# SW6124_A_C_LED.net
KiCad netlist of a schematic drawn in Altium Designer
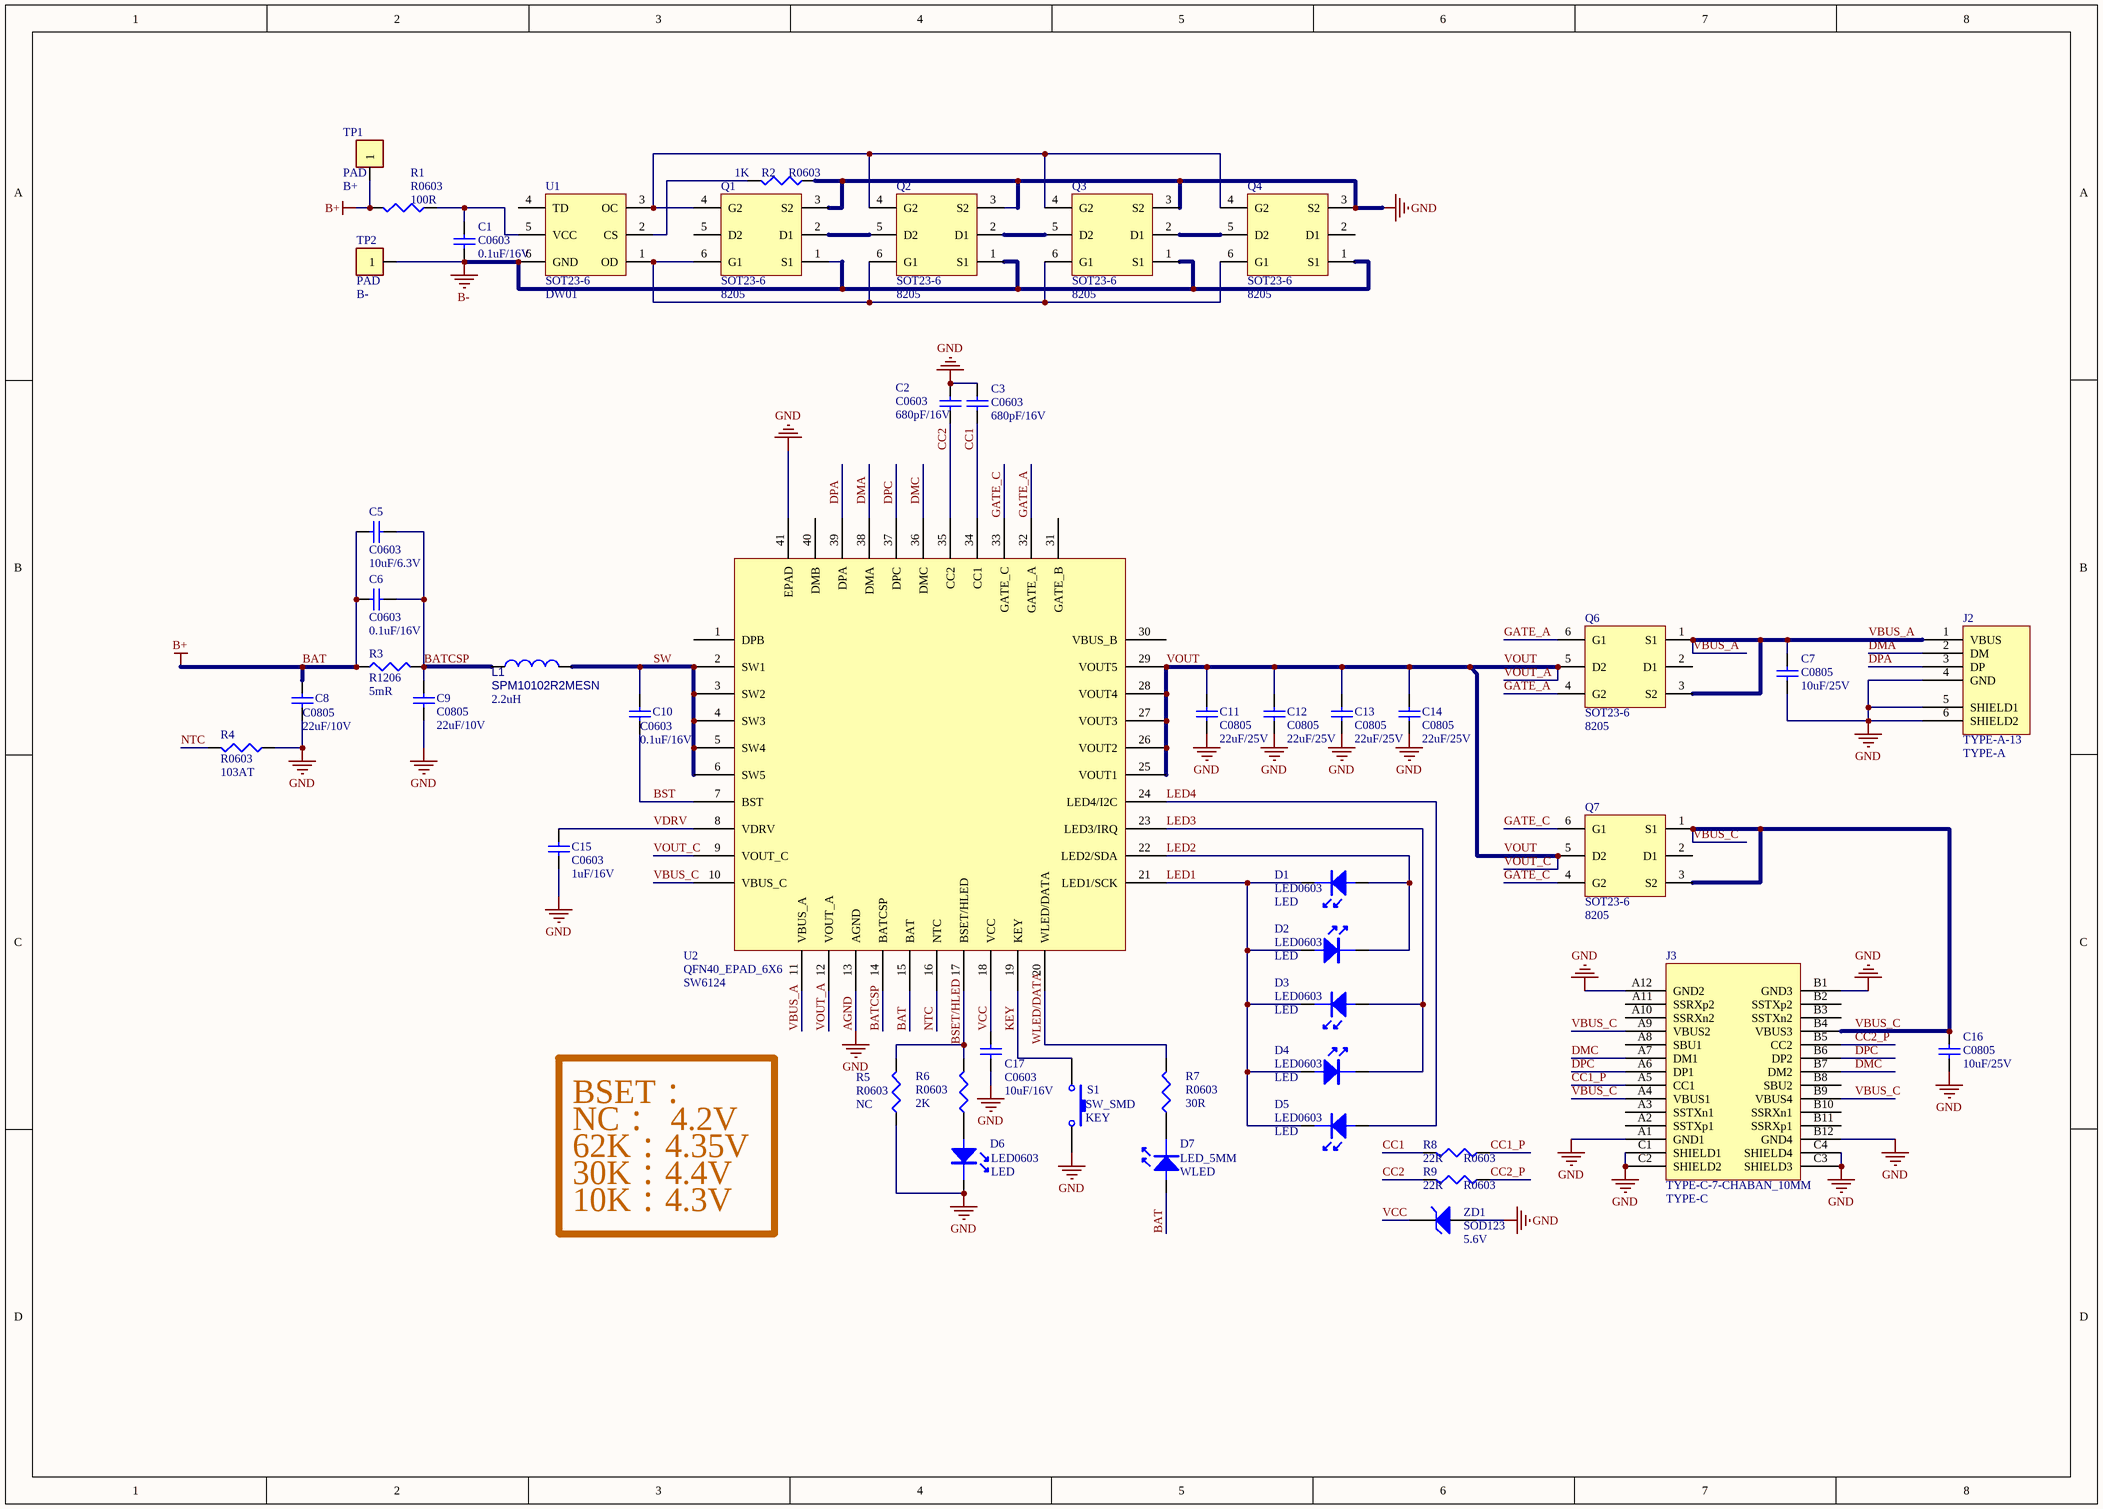
[diagram p0: SW6124+A+C+LED.SchDoc]

(export (version "E")
  (design (tool "Eeschema 10.0.6"))
  (components
    (comp (ref "C1")
      (value "C0603")
      (footprint "C0603")
      (description "Capacitor")
      (fields (field (name "ALTIUM_VALUE") "0.1uF/16V") (field (name "PUBLISHER") "Altium Limited"))
      (libsource (lib "*") (part "Cap"))
    )
    (comp (ref "C2")
      (value "C0603")
      (footprint "C0603")
      (description "Capacitor")
      (fields (field (name "ALTIUM_VALUE") "680pF/16V") (field (name "PUBLISHER") "Altium Limited"))
      (libsource (lib "*") (part "CAP0603"))
    )
    (comp (ref "C3")
      (value "C0603")
      (footprint "C0603")
      (description "Capacitor")
      (fields (field (name "ALTIUM_VALUE") "680pF/16V") (field (name "PUBLISHER") "Altium Limited"))
      (libsource (lib "*") (part "CAP0603"))
    )
    (comp (ref "C5")
      (value "C0603")
      (footprint "C0603")
      (description "Capacitor")
      (fields (field (name "ALTIUM_VALUE") "10uF/6.3V") (field (name "PUBLISHER") "Altium Limited"))
      (libsource (lib "*") (part "CAP0603"))
    )
    (comp (ref "C6")
      (value "C0603")
      (footprint "C0603")
      (description "Capacitor")
      (fields (field (name "ALTIUM_VALUE") "0.1uF/16V") (field (name "PUBLISHER") "Altium Limited"))
      (libsource (lib "*") (part "CAP0603"))
    )
    (comp (ref "C7")
      (value "C0805")
      (footprint "C0805")
      (description "Capacitor")
      (fields (field (name "ALTIUM_VALUE") "10uF/25V") (field (name "PUBLISHER") "Altium Limited"))
      (libsource (lib "*") (part "CAP0603"))
    )
    (comp (ref "C8")
      (value "C0805")
      (footprint "C0805")
      (description "Capacitor")
      (fields (field (name "ALTIUM_VALUE") "22uF/10V") (field (name "PUBLISHER") "Altium Limited"))
      (libsource (lib "*") (part "CAP0805"))
    )
    (comp (ref "C9")
      (value "C0805")
      (footprint "C0805")
      (description "Capacitor")
      (fields (field (name "ALTIUM_VALUE") "22uF/10V") (field (name "PUBLISHER") "Altium Limited"))
      (libsource (lib "*") (part "CAP0805"))
    )
    (comp (ref "C10")
      (value "C0603")
      (footprint "C0603")
      (description "Capacitor")
      (fields (field (name "ALTIUM_VALUE") "0.1uF/16V") (field (name "PUBLISHER") "Altium Limited"))
      (libsource (lib "*") (part "CAP0603"))
    )
    (comp (ref "C11")
      (value "C0805")
      (footprint "C0805")
      (description "Capacitor")
      (fields (field (name "ALTIUM_VALUE") "22uF/25V") (field (name "PUBLISHER") "Altium Limited"))
      (libsource (lib "*") (part "CAP0805"))
    )
    (comp (ref "C12")
      (value "C0805")
      (footprint "C0805")
      (description "Capacitor")
      (fields (field (name "ALTIUM_VALUE") "22uF/25V") (field (name "PUBLISHER") "Altium Limited"))
      (libsource (lib "*") (part "CAP0805"))
    )
    (comp (ref "C13")
      (value "C0805")
      (footprint "C0805")
      (description "Capacitor")
      (fields (field (name "ALTIUM_VALUE") "22uF/25V") (field (name "PUBLISHER") "Altium Limited"))
      (libsource (lib "*") (part "CAP0805"))
    )
    (comp (ref "C14")
      (value "C0805")
      (footprint "C0805")
      (description "Capacitor")
      (fields (field (name "ALTIUM_VALUE") "22uF/25V") (field (name "PUBLISHER") "Altium Limited"))
      (libsource (lib "*") (part "CAP0805"))
    )
    (comp (ref "C15")
      (value "C0603")
      (footprint "C0603")
      (description "Capacitor")
      (fields (field (name "ALTIUM_VALUE") "1uF/16V") (field (name "PUBLISHER") "Altium Limited"))
      (libsource (lib "*") (part "CAP0603"))
    )
    (comp (ref "C16")
      (value "C0805")
      (footprint "C0805")
      (description "Capacitor")
      (fields (field (name "ALTIUM_VALUE") "10uF/25V") (field (name "PUBLISHER") "Altium Limited"))
      (libsource (lib "*") (part "CAP0603"))
    )
    (comp (ref "C17")
      (value "C0603")
      (footprint "C0603")
      (description "Capacitor")
      (fields (field (name "ALTIUM_VALUE") "10uF/16V") (field (name "PUBLISHER") "Altium Limited"))
      (libsource (lib "*") (part "CAP0603"))
    )
    (comp (ref "D1") (value "LED") (footprint "LED0603") (libsource (lib "*") (part "LED")))
    (comp (ref "D2") (value "LED") (footprint "LED0603") (libsource (lib "*") (part "LED")))
    (comp (ref "D3") (value "LED") (footprint "LED0603") (libsource (lib "*") (part "LED")))
    (comp (ref "D4") (value "LED") (footprint "LED0603") (libsource (lib "*") (part "LED")))
    (comp (ref "D5") (value "LED") (footprint "LED0603") (libsource (lib "*") (part "LED")))
    (comp (ref "D6") (value "LED") (footprint "LED0603") (libsource (lib "*") (part "LED")))
    (comp (ref "D7")
      (value "WLED")
      (footprint "LED_5MM")
      (fields (field (name "FOOTPRINF") "LED_5MM") (field (name "Comment") "LED_5MM"))
      (libsource (lib "*") (part "LED"))
    )
    (comp (ref "J2")
      (value "TYPE-A")
      (footprint "TYPE-A-13")
      (fields (field (name "FOOTPRINF") "TYPE-A-13") (field (name "Comment") "TYPE-A-1"))
      (libsource (lib "*") (part "TYPE-A-1"))
    )
    (comp (ref "J3")
      (value "TYPE-C")
      (footprint "TYPE-C-7-CHABAN_10MM")
      (libsource (lib "*") (part "TYPE-C"))
    )
    (comp (ref "L1")
      (value "SPM10102R2MESN")
      (footprint "INDUCTOR_SPM1010")
      (fields (field (name "ALTIUM_VALUE") "2.2uH"))
      (libsource (lib "*") (part "INDUCTOR"))
    )
    (comp (ref "Q1")
      (value "8205")
      (footprint "SOT23-6")
      (fields (field (name "FOOTPRINF") "SOT23-6"))
      (libsource (lib "*") (part "8205B"))
    )
    (comp (ref "Q2")
      (value "8205")
      (footprint "SOT23-6")
      (fields (field (name "FOOTPRINF") "SOT23-6"))
      (libsource (lib "*") (part "8205B"))
    )
    (comp (ref "Q3")
      (value "8205")
      (footprint "SOT23-6")
      (fields (field (name "FOOTPRINF") "SOT23-6"))
      (libsource (lib "*") (part "8205B"))
    )
    (comp (ref "Q4")
      (value "8205")
      (footprint "SOT23-6")
      (fields (field (name "FOOTPRINF") "SOT23-6"))
      (libsource (lib "*") (part "8205B"))
    )
    (comp (ref "Q6")
      (value "8205")
      (footprint "SOT23-6")
      (fields (field (name "FOOTPRINF") "SOT23-6"))
      (libsource (lib "") (part "8205B_1"))
    )
    (comp (ref "Q7")
      (value "8205")
      (footprint "SOT23-6")
      (fields (field (name "FOOTPRINF") "SOT23-6"))
      (libsource (lib "") (part "8205B_1"))
    )
    (comp (ref "R1")
      (value "R0603")
      (footprint "R0603")
      (description "Resistor")
      (fields (field (name "ALTIUM_VALUE") "100R") (field (name "PUBLISHER") "Altium Limited"))
      (libsource (lib "*") (part "Res3"))
    )
    (comp (ref "R2")
      (value "R0603")
      (footprint "R0603")
      (description "Resistor")
      (fields (field (name "ALTIUM_VALUE") "1K") (field (name "PUBLISHER") "Altium Limited"))
      (libsource (lib "*") (part "Res3"))
    )
    (comp (ref "R3")
      (value "R1206")
      (footprint "R1206")
      (description "Resistor")
      (fields (field (name "ALTIUM_VALUE") "5mR") (field (name "PUBLISHER") "Altium Limited"))
      (libsource (lib "*") (part "RES"))
    )
    (comp (ref "R4")
      (value "R0603")
      (footprint "R0603")
      (description "Resistor")
      (fields (field (name "ALTIUM_VALUE") "103AT") (field (name "PUBLISHER") "Altium Limited"))
      (libsource (lib "*") (part "RES"))
    )
    (comp (ref "R5")
      (value "R0603")
      (footprint "R0603")
      (description "Resistor")
      (fields (field (name "ALTIUM_VALUE") "NC") (field (name "PUBLISHER") "Altium Limited"))
      (libsource (lib "*") (part "RES"))
    )
    (comp (ref "R6")
      (value "R0603")
      (footprint "R0603")
      (description "Resistor")
      (fields (field (name "ALTIUM_VALUE") "2K") (field (name "PUBLISHER") "Altium Limited"))
      (libsource (lib "*") (part "RES"))
    )
    (comp (ref "R7")
      (value "R0603")
      (footprint "R0603")
      (description "Resistor")
      (fields (field (name "ALTIUM_VALUE") "30R") (field (name "PUBLISHER") "Altium Limited"))
      (libsource (lib "*") (part "RES"))
    )
    (comp (ref "R8")
      (value "R0603")
      (footprint "R0603")
      (description "Resistor")
      (fields (field (name "ALTIUM_VALUE") "22R") (field (name "PUBLISHER") "Altium Limited"))
      (libsource (lib "*") (part "RES"))
    )
    (comp (ref "R9")
      (value "R0603")
      (footprint "R0603")
      (description "Resistor")
      (fields (field (name "ALTIUM_VALUE") "22R") (field (name "PUBLISHER") "Altium Limited"))
      (libsource (lib "*") (part "RES"))
    )
    (comp (ref "S1")
      (value "KEY")
      (footprint "SW_SMD")
      (fields (field (name "FOOTPRINF") "SW_SMD"))
      (libsource (lib "*") (part "SW K"))
    )
    (comp (ref "TP1") (value "B+") (footprint "PAD") (libsource (lib "") (part "Test Point_1")))
    (comp (ref "TP2") (value "B-") (footprint "PAD") (libsource (lib "*") (part "Test Point")))
    (comp (ref "U1")
      (value "DW01")
      (footprint "SOT23-6")
      (fields (field (name "FOOTPRINF") "SOT23-6"))
      (libsource (lib "*") (part "DW01"))
    )
    (comp (ref "U2")
      (value "SW6124")
      (footprint "QFN40_EPAD_6X6")
      (libsource (lib "TEST") (part "SW6106_AFC"))
    )
    (comp (ref "ZD1")
      (value "SOD123")
      (footprint "SOD-123")
      (description "Zener Diode")
      (fields (field (name "ALTIUM_UNNAMED_1") "5.6V"))
      (libsource (lib "Miscellaneous Devices") (part "D Zener"))
    )
  )
  (nets
    (net (code "1") (name "/BATCSP") (class "Default")
      (node (ref "C5") (pin "2") (pinfunction "2_2") (pintype "passive"))
      (node (ref "C6") (pin "2") (pinfunction "2_2") (pintype "passive"))
      (node (ref "C9") (pin "2") (pinfunction "2_2") (pintype "passive"))
      (node (ref "L1") (pin "1") (pinfunction "1_1") (pintype "passive"))
      (node (ref "R3") (pin "2") (pinfunction "2_2") (pintype "passive"))
      (node (ref "U2") (pin "14") (pinfunction "BATCSP_14") (pintype "passive"))
    )
    (net (code "2") (name "/BSET{slash}HLED") (class "Default")
      (node (ref "R5") (pin "2") (pinfunction "2_2") (pintype "passive"))
      (node (ref "R6") (pin "2") (pinfunction "2_2") (pintype "passive"))
      (node (ref "U2") (pin "17") (pinfunction "BSET/HLED_17") (pintype "passive"))
    )
    (net (code "3") (name "/BST") (class "Default")
      (node (ref "C10") (pin "1") (pinfunction "1_1") (pintype "passive"))
      (node (ref "U2") (pin "7") (pinfunction "BST_7") (pintype "passive"))
    )
    (net (code "4") (name "/CC1") (class "Default")
      (node (ref "C3") (pin "1") (pinfunction "1_1") (pintype "passive"))
      (node (ref "R8") (pin "2") (pinfunction "2_2") (pintype "passive"))
      (node (ref "U2") (pin "34") (pinfunction "CC1_34") (pintype "passive"))
    )
    (net (code "5") (name "/CC1_P") (class "Default")
      (node (ref "J3") (pin "A5") (pinfunction "CC1_A5") (pintype "passive"))
      (node (ref "R8") (pin "1") (pinfunction "1_1") (pintype "passive"))
    )
    (net (code "6") (name "/CC2") (class "Default")
      (node (ref "C2") (pin "1") (pinfunction "1_1") (pintype "passive"))
      (node (ref "R9") (pin "2") (pinfunction "2_2") (pintype "passive"))
      (node (ref "U2") (pin "35") (pinfunction "CC2_35") (pintype "passive"))
    )
    (net (code "7") (name "/CC2_P") (class "Default")
      (node (ref "J3") (pin "B5") (pinfunction "CC2_B5") (pintype "passive"))
      (node (ref "R9") (pin "1") (pinfunction "1_1") (pintype "passive"))
    )
    (net (code "8") (name "/DMA") (class "Default")
      (node (ref "J2") (pin "2") (pinfunction "DM_2") (pintype "passive"))
      (node (ref "U2") (pin "38") (pinfunction "DMA_38") (pintype "passive"))
    )
    (net (code "9") (name "/DMC") (class "Default")
      (node (ref "J3") (pin "A7") (pinfunction "DM1_A7") (pintype "passive"))
      (node (ref "J3") (pin "B7") (pinfunction "DM2_B7") (pintype "passive"))
      (node (ref "U2") (pin "36") (pinfunction "DMC_36") (pintype "passive"))
    )
    (net (code "10") (name "/DPA") (class "Default")
      (node (ref "J2") (pin "3") (pinfunction "DP_3") (pintype "passive"))
      (node (ref "U2") (pin "39") (pinfunction "DPA_39") (pintype "passive"))
    )
    (net (code "11") (name "/DPC") (class "Default")
      (node (ref "J3") (pin "A6") (pinfunction "DP1_A6") (pintype "passive"))
      (node (ref "J3") (pin "B6") (pinfunction "DP2_B6") (pintype "passive"))
      (node (ref "U2") (pin "37") (pinfunction "DPC_37") (pintype "passive"))
    )
    (net (code "12") (name "/GATE_A") (class "Default")
      (node (ref "Q6") (pin "4") (pinfunction "G2_4") (pintype "passive"))
      (node (ref "Q6") (pin "6") (pinfunction "G1_6") (pintype "passive"))
      (node (ref "U2") (pin "32") (pinfunction "GATE_A_32") (pintype "passive"))
    )
    (net (code "13") (name "/GATE_C") (class "Default")
      (node (ref "Q7") (pin "4") (pinfunction "G2_4") (pintype "passive"))
      (node (ref "Q7") (pin "6") (pinfunction "G1_6") (pintype "passive"))
      (node (ref "U2") (pin "33") (pinfunction "GATE_C_33") (pintype "passive"))
    )
    (net (code "14") (name "/KEY") (class "Default")
      (node (ref "S1") (pin "1") (pinfunction "1_1") (pintype "passive"))
      (node (ref "U2") (pin "19") (pinfunction "KEY_19") (pintype "passive"))
    )
    (net (code "15") (name "/LED1") (class "Default")
      (node (ref "D1") (pin "2") (pinfunction "K_2") (pintype "passive"))
      (node (ref "D2") (pin "1") (pinfunction "A_1") (pintype "passive"))
      (node (ref "D3") (pin "2") (pinfunction "K_2") (pintype "passive"))
      (node (ref "D4") (pin "1") (pinfunction "A_1") (pintype "passive"))
      (node (ref "D5") (pin "2") (pinfunction "K_2") (pintype "passive"))
      (node (ref "U2") (pin "21") (pinfunction "LED1/SCK_21") (pintype "passive"))
    )
    (net (code "16") (name "/LED2") (class "Default")
      (node (ref "D1") (pin "1") (pinfunction "A_1") (pintype "passive"))
      (node (ref "D2") (pin "2") (pinfunction "K_2") (pintype "passive"))
      (node (ref "U2") (pin "22") (pinfunction "LED2/SDA_22") (pintype "passive"))
    )
    (net (code "17") (name "/LED3") (class "Default")
      (node (ref "D3") (pin "1") (pinfunction "A_1") (pintype "passive"))
      (node (ref "D4") (pin "2") (pinfunction "K_2") (pintype "passive"))
      (node (ref "U2") (pin "23") (pinfunction "LED3/IRQ_23") (pintype "passive"))
    )
    (net (code "18") (name "/LED4") (class "Default")
      (node (ref "D5") (pin "1") (pinfunction "A_1") (pintype "passive"))
      (node (ref "U2") (pin "24") (pinfunction "LED4/I2C_24") (pintype "passive"))
    )
    (net (code "19") (name "/NTC") (class "Default")
      (node (ref "R4") (pin "2") (pinfunction "2_2") (pintype "passive"))
      (node (ref "U2") (pin "16") (pinfunction "NTC_16") (pintype "passive"))
    )
    (net (code "20") (name "/SW") (class "Default")
      (node (ref "C10") (pin "2") (pinfunction "2_2") (pintype "passive"))
      (node (ref "L1") (pin "2") (pinfunction "2_2") (pintype "passive"))
      (node (ref "U2") (pin "2") (pinfunction "SW1_2") (pintype "passive"))
      (node (ref "U2") (pin "3") (pinfunction "SW2_3") (pintype "passive"))
      (node (ref "U2") (pin "4") (pinfunction "SW3_4") (pintype "passive"))
      (node (ref "U2") (pin "5") (pinfunction "SW4_5") (pintype "passive"))
      (node (ref "U2") (pin "6") (pinfunction "SW5_6") (pintype "passive"))
    )
    (net (code "21") (name "/VBUS_A") (class "Default")
      (node (ref "C7") (pin "2") (pinfunction "2_2") (pintype "passive"))
      (node (ref "J2") (pin "1") (pinfunction "VBUS_1") (pintype "passive"))
      (node (ref "Q6") (pin "1") (pinfunction "S1_1") (pintype "passive"))
      (node (ref "Q6") (pin "3") (pinfunction "S2_3") (pintype "passive"))
      (node (ref "U2") (pin "11") (pinfunction "VBUS_A_11") (pintype "passive"))
    )
    (net (code "22") (name "/VBUS_C") (class "Default")
      (node (ref "C16") (pin "2") (pinfunction "2_2") (pintype "passive"))
      (node (ref "J3") (pin "A4") (pinfunction "VBUS1_A4") (pintype "passive"))
      (node (ref "J3") (pin "A9") (pinfunction "VBUS2_A9") (pintype "passive"))
      (node (ref "J3") (pin "B4") (pinfunction "VBUS3_B4") (pintype "passive"))
      (node (ref "J3") (pin "B9") (pinfunction "VBUS4_B9") (pintype "passive"))
      (node (ref "Q7") (pin "1") (pinfunction "S1_1") (pintype "passive"))
      (node (ref "Q7") (pin "3") (pinfunction "S2_3") (pintype "passive"))
      (node (ref "U2") (pin "10") (pinfunction "VBUS_C_10") (pintype "passive"))
    )
    (net (code "23") (name "/VCC") (class "Default")
      (node (ref "C17") (pin "2") (pinfunction "2_2") (pintype "passive"))
      (node (ref "U2") (pin "18") (pinfunction "VCC_18") (pintype "passive"))
      (node (ref "ZD1") (pin "2") (pinfunction "K_2") (pintype "passive"))
    )
    (net (code "24") (name "/VDRV") (class "Default")
      (node (ref "C15") (pin "2") (pinfunction "2_2") (pintype "passive"))
      (node (ref "U2") (pin "8") (pinfunction "VDRV_8") (pintype "passive"))
    )
    (net (code "25") (name "/VOUT") (class "Default")
      (node (ref "C11") (pin "2") (pinfunction "2_2") (pintype "passive"))
      (node (ref "C12") (pin "2") (pinfunction "2_2") (pintype "passive"))
      (node (ref "C13") (pin "2") (pinfunction "2_2") (pintype "passive"))
      (node (ref "C14") (pin "2") (pinfunction "2_2") (pintype "passive"))
      (node (ref "Q6") (pin "5") (pinfunction "D2_5") (pintype "passive"))
      (node (ref "Q7") (pin "5") (pinfunction "D2_5") (pintype "passive"))
      (node (ref "U2") (pin "12") (pinfunction "VOUT_A_12") (pintype "passive"))
      (node (ref "U2") (pin "25") (pinfunction "VOUT1_25") (pintype "passive"))
      (node (ref "U2") (pin "26") (pinfunction "VOUT2_26") (pintype "passive"))
      (node (ref "U2") (pin "27") (pinfunction "VOUT3_27") (pintype "passive"))
      (node (ref "U2") (pin "28") (pinfunction "VOUT4_28") (pintype "passive"))
      (node (ref "U2") (pin "29") (pinfunction "VOUT5_29") (pintype "passive"))
      (node (ref "U2") (pin "9") (pinfunction "VOUT_C_9") (pintype "passive"))
    )
    (net (code "26") (name "/WLED{slash}DATA") (class "Default")
      (node (ref "R7") (pin "2") (pinfunction "2_2") (pintype "passive"))
      (node (ref "U2") (pin "20") (pinfunction "WLED/DATA_20") (pintype "passive"))
    )
    (net (code "27") (name "B+") (class "Default")
      (node (ref "C5") (pin "1") (pinfunction "1_1") (pintype "passive"))
      (node (ref "C6") (pin "1") (pinfunction "1_1") (pintype "passive"))
      (node (ref "C8") (pin "2") (pinfunction "2_2") (pintype "passive"))
      (node (ref "D7") (pin "1") (pinfunction "A_1") (pintype "passive"))
      (node (ref "R1") (pin "2") (pinfunction "2_2") (pintype "passive"))
      (node (ref "R3") (pin "1") (pinfunction "1_1") (pintype "passive"))
      (node (ref "TP1") (pin "1") (pinfunction "1_1") (pintype "passive"))
      (node (ref "U2") (pin "15") (pinfunction "BAT_15") (pintype "passive"))
    )
    (net (code "28") (name "B-") (class "Default")
      (node (ref "C1") (pin "1") (pinfunction "1_1") (pintype "passive"))
      (node (ref "Q1") (pin "1") (pinfunction "S1_1") (pintype "passive"))
      (node (ref "Q2") (pin "1") (pinfunction "S1_1") (pintype "passive"))
      (node (ref "Q3") (pin "1") (pinfunction "S1_1") (pintype "passive"))
      (node (ref "Q4") (pin "1") (pinfunction "S1_1") (pintype "passive"))
      (node (ref "TP2") (pin "1") (pinfunction "1_1") (pintype "passive"))
      (node (ref "U1") (pin "6") (pinfunction "GND_6") (pintype "passive"))
    )
    (net (code "29") (name "GND") (class "Default")
      (node (ref "C11") (pin "1") (pinfunction "1_1") (pintype "passive"))
      (node (ref "C12") (pin "1") (pinfunction "1_1") (pintype "passive"))
      (node (ref "C13") (pin "1") (pinfunction "1_1") (pintype "passive"))
      (node (ref "C14") (pin "1") (pinfunction "1_1") (pintype "passive"))
      (node (ref "C15") (pin "1") (pinfunction "1_1") (pintype "passive"))
      (node (ref "C16") (pin "1") (pinfunction "1_1") (pintype "passive"))
      (node (ref "C17") (pin "1") (pinfunction "1_1") (pintype "passive"))
      (node (ref "C2") (pin "2") (pinfunction "2_2") (pintype "passive"))
      (node (ref "C3") (pin "2") (pinfunction "2_2") (pintype "passive"))
      (node (ref "C7") (pin "1") (pinfunction "1_1") (pintype "passive"))
      (node (ref "C8") (pin "1") (pinfunction "1_1") (pintype "passive"))
      (node (ref "C9") (pin "1") (pinfunction "1_1") (pintype "passive"))
      (node (ref "D6") (pin "2") (pinfunction "K_2") (pintype "passive"))
      (node (ref "J2") (pin "4") (pinfunction "GND_4") (pintype "passive"))
      (node (ref "J2") (pin "5") (pinfunction "SHIELD1_5") (pintype "passive"))
      (node (ref "J2") (pin "6") (pinfunction "SHIELD2_6") (pintype "passive"))
      (node (ref "J3") (pin "A1") (pinfunction "GND1_A1") (pintype "passive"))
      (node (ref "J3") (pin "A12") (pinfunction "GND2_A12") (pintype "passive"))
      (node (ref "J3") (pin "B1") (pinfunction "GND3_B1") (pintype "passive"))
      (node (ref "J3") (pin "B12") (pinfunction "GND4_B12") (pintype "passive"))
      (node (ref "J3") (pin "C1") (pinfunction "SHIELD1_C1") (pintype "passive"))
      (node (ref "J3") (pin "C2") (pinfunction "SHIELD2_C2") (pintype "passive"))
      (node (ref "J3") (pin "C3") (pinfunction "SHIELD3_C3") (pintype "passive"))
      (node (ref "J3") (pin "C4") (pinfunction "SHIELD4_C4") (pintype "passive"))
      (node (ref "Q1") (pin "3") (pinfunction "S2_3") (pintype "passive"))
      (node (ref "Q2") (pin "3") (pinfunction "S2_3") (pintype "passive"))
      (node (ref "Q3") (pin "3") (pinfunction "S2_3") (pintype "passive"))
      (node (ref "Q4") (pin "3") (pinfunction "S2_3") (pintype "passive"))
      (node (ref "R2") (pin "1") (pinfunction "1_1") (pintype "passive"))
      (node (ref "R4") (pin "1") (pinfunction "1_1") (pintype "passive"))
      (node (ref "R5") (pin "1") (pinfunction "1_1") (pintype "passive"))
      (node (ref "S1") (pin "2") (pinfunction "2_2") (pintype "passive"))
      (node (ref "U2") (pin "13") (pinfunction "AGND_13") (pintype "passive"))
      (node (ref "U2") (pin "41") (pinfunction "EPAD_41") (pintype "passive"))
      (node (ref "ZD1") (pin "1") (pinfunction "A_1") (pintype "passive"))
    )
    (net (code "30") (name "Net-(D6-A)") (class "Default")
      (node (ref "D6") (pin "1") (pinfunction "A_1") (pintype "passive"))
      (node (ref "R6") (pin "1") (pinfunction "1_1") (pintype "passive"))
    )
    (net (code "31") (name "Net-(D7-K)") (class "Default")
      (node (ref "D7") (pin "2") (pinfunction "K_2") (pintype "passive"))
      (node (ref "R7") (pin "1") (pinfunction "1_1") (pintype "passive"))
    )
    (net (code "32") (name "Net-(Q1-D1)") (class "Default")
      (node (ref "Q1") (pin "2") (pinfunction "D1_2") (pintype "passive"))
      (node (ref "Q2") (pin "5") (pinfunction "D2_5") (pintype "passive"))
    )
    (net (code "33") (name "Net-(Q1-G1)") (class "Default")
      (node (ref "Q1") (pin "6") (pinfunction "G1_6") (pintype "passive"))
      (node (ref "Q2") (pin "6") (pinfunction "G1_6") (pintype "passive"))
      (node (ref "Q3") (pin "6") (pinfunction "G1_6") (pintype "passive"))
      (node (ref "Q4") (pin "6") (pinfunction "G1_6") (pintype "passive"))
      (node (ref "U1") (pin "1") (pinfunction "OD_1") (pintype "passive"))
    )
    (net (code "34") (name "Net-(Q1-G2)") (class "Default")
      (node (ref "Q1") (pin "4") (pinfunction "G2_4") (pintype "passive"))
      (node (ref "Q2") (pin "4") (pinfunction "G2_4") (pintype "passive"))
      (node (ref "Q3") (pin "4") (pinfunction "G2_4") (pintype "passive"))
      (node (ref "Q4") (pin "4") (pinfunction "G2_4") (pintype "passive"))
      (node (ref "U1") (pin "3") (pinfunction "OC_3") (pintype "passive"))
    )
    (net (code "35") (name "Net-(Q2-D1)") (class "Default")
      (node (ref "Q2") (pin "2") (pinfunction "D1_2") (pintype "passive"))
      (node (ref "Q3") (pin "5") (pinfunction "D2_5") (pintype "passive"))
    )
    (net (code "36") (name "Net-(Q3-D1)") (class "Default")
      (node (ref "Q3") (pin "2") (pinfunction "D1_2") (pintype "passive"))
      (node (ref "Q4") (pin "5") (pinfunction "D2_5") (pintype "passive"))
    )
    (net (code "37") (name "Net-(U1-CS)") (class "Default")
      (node (ref "R2") (pin "2") (pinfunction "2_2") (pintype "passive"))
      (node (ref "U1") (pin "2") (pinfunction "CS_2") (pintype "passive"))
    )
    (net (code "38") (name "Net-(U1-VCC)") (class "Default")
      (node (ref "C1") (pin "2") (pinfunction "2_2") (pintype "passive"))
      (node (ref "R1") (pin "1") (pinfunction "1_1") (pintype "passive"))
      (node (ref "U1") (pin "5") (pinfunction "VCC_5") (pintype "passive"))
    )
    (net (code "39") (name "unconnected-(J3-SBU1-PadA8)") (class "Default")
      (node (ref "J3") (pin "A8") (pinfunction "SBU1_A8") (pintype "passive"))
    )
    (net (code "40") (name "unconnected-(J3-SBU2-PadB8)") (class "Default")
      (node (ref "J3") (pin "B8") (pinfunction "SBU2_B8") (pintype "passive"))
    )
    (net (code "41") (name "unconnected-(J3-SSRXn1-PadB10)") (class "Default")
      (node (ref "J3") (pin "B10") (pinfunction "SSRXn1_B10") (pintype "passive"))
    )
    (net (code "42") (name "unconnected-(J3-SSRXn2-PadA10)") (class "Default")
      (node (ref "J3") (pin "A10") (pinfunction "SSRXn2_A10") (pintype "passive"))
    )
    (net (code "43") (name "unconnected-(J3-SSRXp1-PadB11)") (class "Default")
      (node (ref "J3") (pin "B11") (pinfunction "SSRXp1_B11") (pintype "passive"))
    )
    (net (code "44") (name "unconnected-(J3-SSRXp2-PadA11)") (class "Default")
      (node (ref "J3") (pin "A11") (pinfunction "SSRXp2_A11") (pintype "passive"))
    )
    (net (code "45") (name "unconnected-(J3-SSTXn1-PadA3)") (class "Default")
      (node (ref "J3") (pin "A3") (pinfunction "SSTXn1_A3") (pintype "passive"))
    )
    (net (code "46") (name "unconnected-(J3-SSTXn2-PadB3)") (class "Default")
      (node (ref "J3") (pin "B3") (pinfunction "SSTXn2_B3") (pintype "passive"))
    )
    (net (code "47") (name "unconnected-(J3-SSTXp1-PadA2)") (class "Default")
      (node (ref "J3") (pin "A2") (pinfunction "SSTXp1_A2") (pintype "passive"))
    )
    (net (code "48") (name "unconnected-(J3-SSTXp2-PadB2)") (class "Default")
      (node (ref "J3") (pin "B2") (pinfunction "SSTXp2_B2") (pintype "passive"))
    )
    (net (code "49") (name "unconnected-(Q1-D2-Pad5)") (class "Default")
      (node (ref "Q1") (pin "5") (pinfunction "D2_5") (pintype "passive"))
    )
    (net (code "50") (name "unconnected-(Q4-D1-Pad2)") (class "Default")
      (node (ref "Q4") (pin "2") (pinfunction "D1_2") (pintype "passive"))
    )
    (net (code "51") (name "unconnected-(Q6-D1-Pad2)") (class "Default")
      (node (ref "Q6") (pin "2") (pinfunction "D1_2") (pintype "passive"))
    )
    (net (code "52") (name "unconnected-(Q7-D1-Pad2)") (class "Default")
      (node (ref "Q7") (pin "2") (pinfunction "D1_2") (pintype "passive"))
    )
    (net (code "53") (name "unconnected-(U1-TD-Pad4)") (class "Default")
      (node (ref "U1") (pin "4") (pinfunction "TD_4") (pintype "passive"))
    )
    (net (code "54") (name "unconnected-(U2-DMB-Pad40)") (class "Default")
      (node (ref "U2") (pin "40") (pinfunction "DMB_40") (pintype "passive"))
    )
    (net (code "55") (name "unconnected-(U2-DPB-Pad1)") (class "Default")
      (node (ref "U2") (pin "1") (pinfunction "DPB_1") (pintype "passive"))
    )
    (net (code "56") (name "unconnected-(U2-GATE_B-Pad31)") (class "Default")
      (node (ref "U2") (pin "31") (pinfunction "GATE_B_31") (pintype "passive"))
    )
    (net (code "57") (name "unconnected-(U2-VBUS_B-Pad30)") (class "Default")
      (node (ref "U2") (pin "30") (pinfunction "VBUS_B_30") (pintype "passive"))
    )
  )
)
